# 12-DSP_PROCESSOR_2-OF-3.net
KiCad netlist of a schematic drawn in Altium Designer
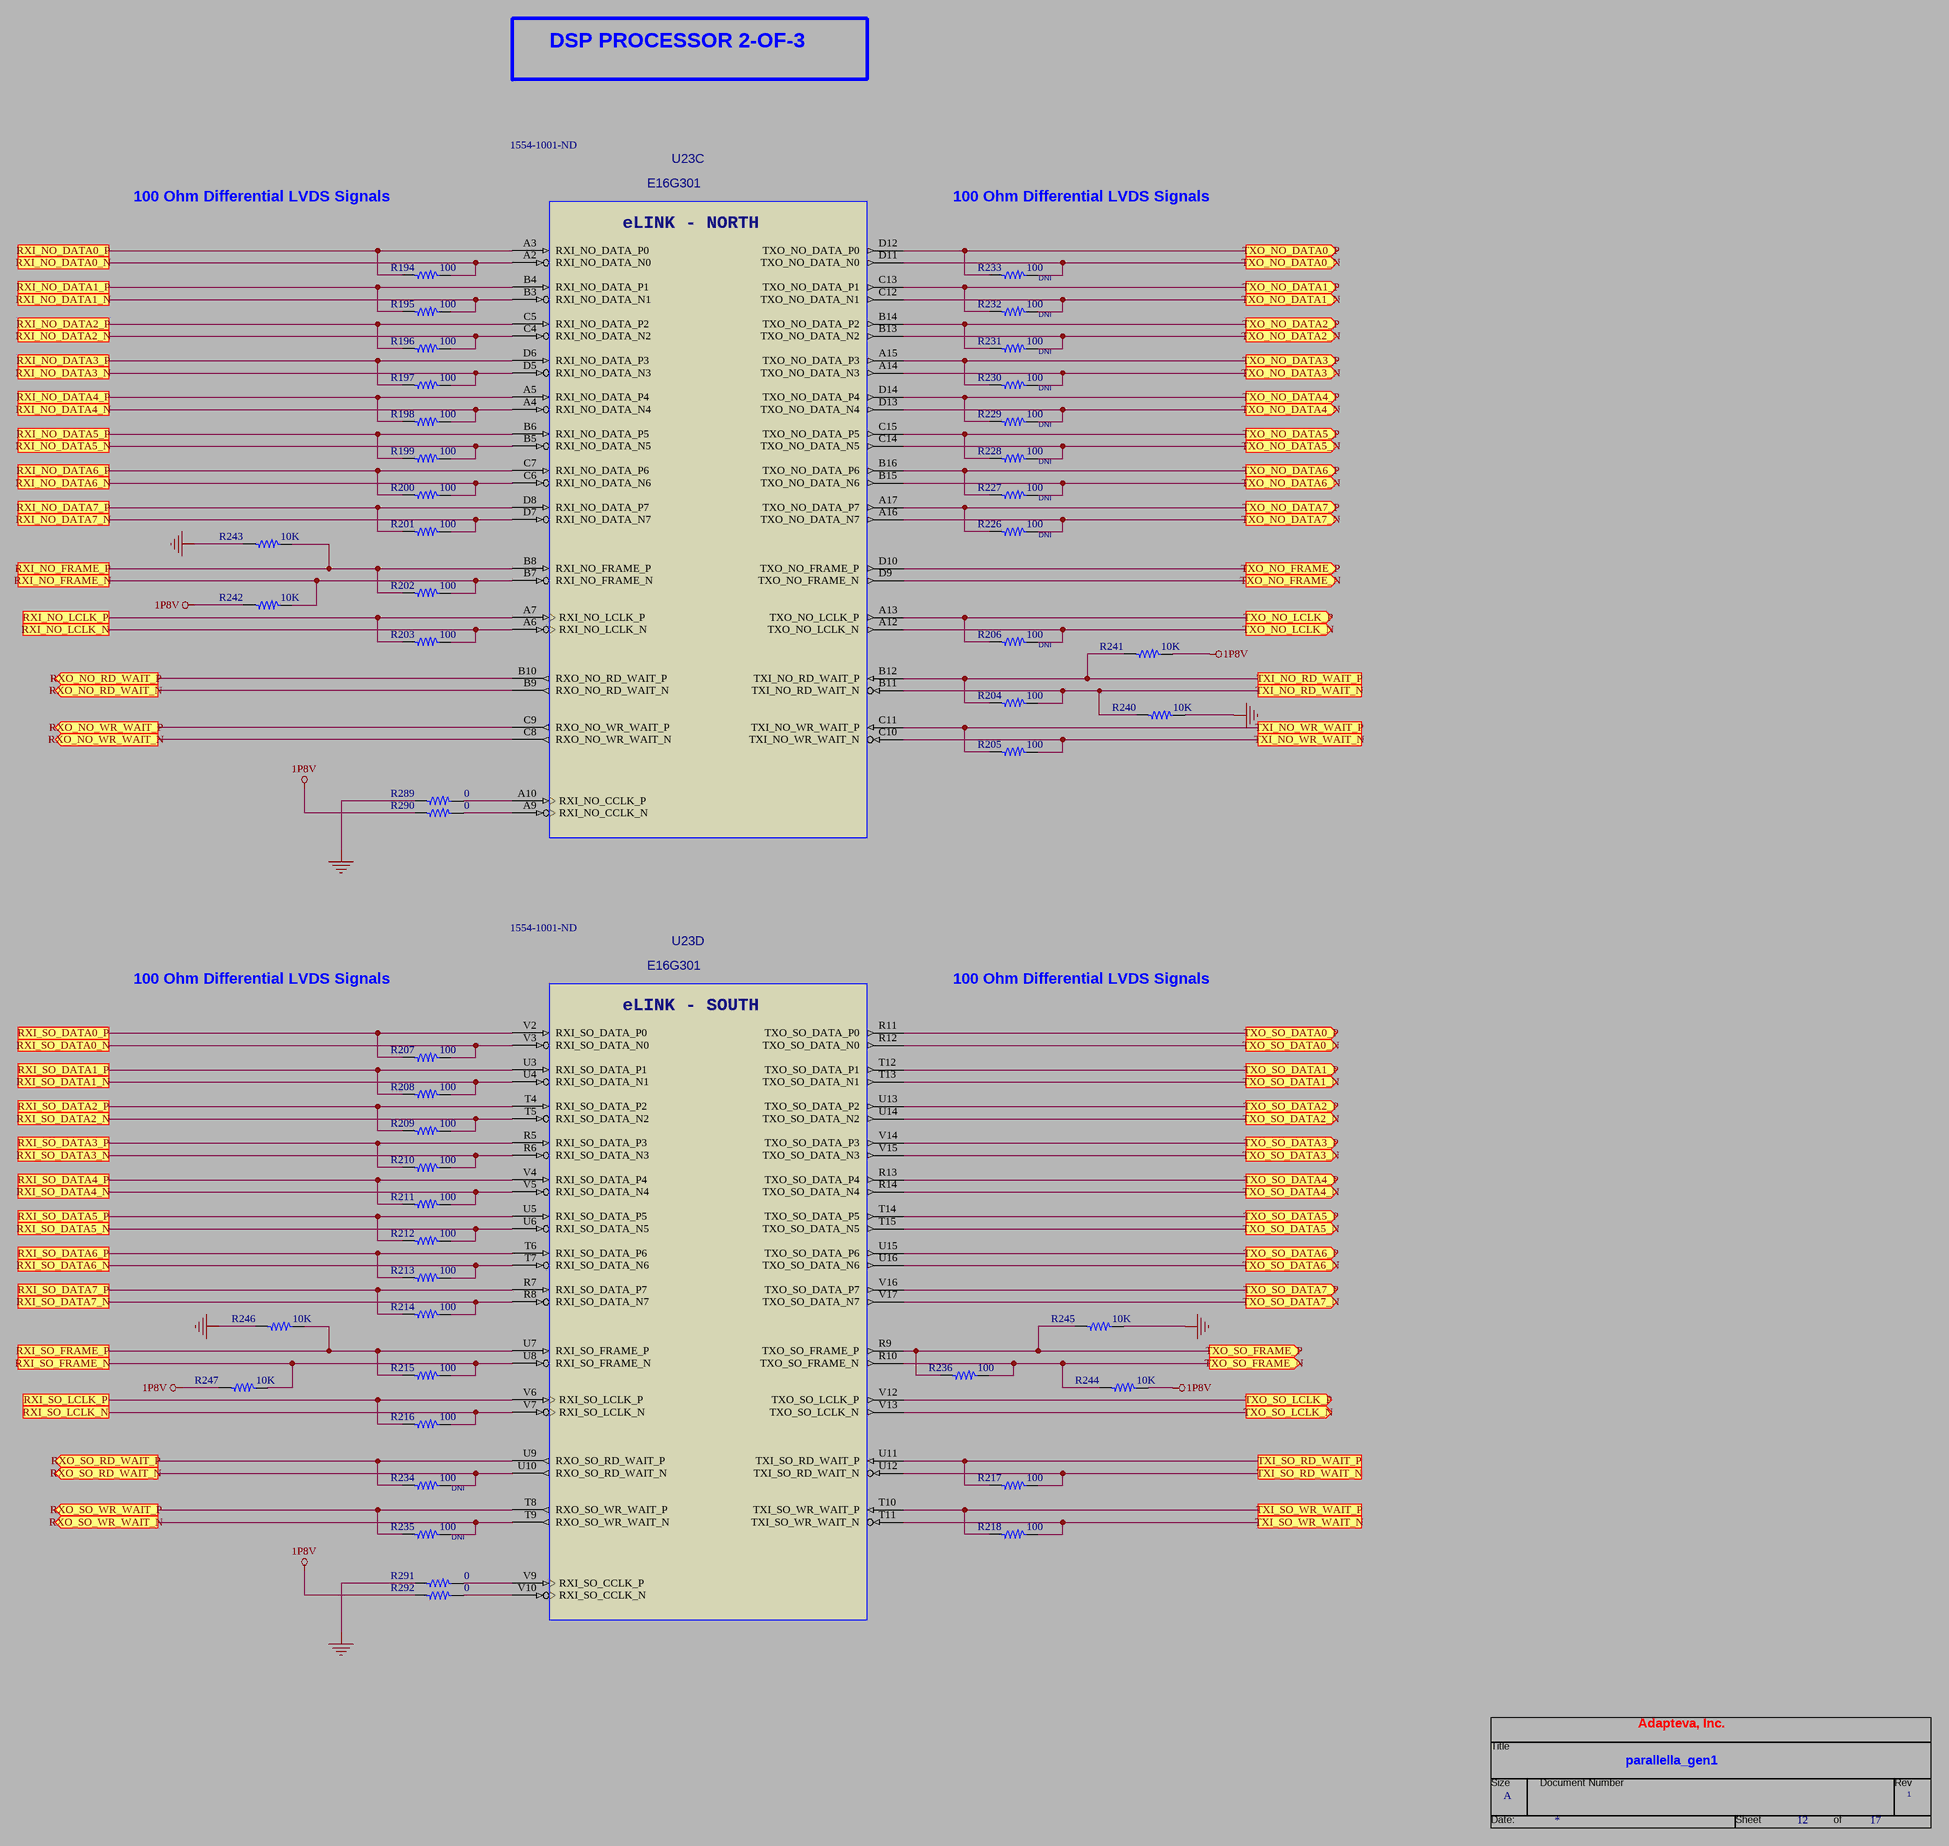
[diagram p0: 12-DSP PROCESSOR 2-OF-3.SchDoc]

(export (version "E")
  (design (tool "Eeschema 10.0.6"))
  (components
    (comp (ref "R194")
      (value "100")
      (footprint "R0402")
      (description "RES, 0402, 100, 1%")
      (fields (field (name "MFG PART NO") "CRCW0402100RFKED") (field (name "MFG") "VISHAY"))
      (libsource (lib "*") (part "RES0402_100"))
    )
    (comp (ref "R195")
      (value "100")
      (footprint "R0402")
      (description "RES, 0402, 100, 1%")
      (fields (field (name "MFG PART NO") "CRCW0402100RFKED") (field (name "MFG") "VISHAY"))
      (libsource (lib "*") (part "RES0402_100"))
    )
    (comp (ref "R196")
      (value "100")
      (footprint "R0402")
      (description "RES, 0402, 100, 1%")
      (fields (field (name "MFG PART NO") "CRCW0402100RFKED") (field (name "MFG") "VISHAY"))
      (libsource (lib "*") (part "RES0402_100"))
    )
    (comp (ref "R197")
      (value "100")
      (footprint "R0402")
      (description "RES, 0402, 100, 1%")
      (fields (field (name "MFG PART NO") "CRCW0402100RFKED") (field (name "MFG") "VISHAY"))
      (libsource (lib "*") (part "RES0402_100"))
    )
    (comp (ref "R198")
      (value "100")
      (footprint "R0402")
      (description "RES, 0402, 100, 1%")
      (fields (field (name "MFG PART NO") "CRCW0402100RFKED") (field (name "MFG") "VISHAY"))
      (libsource (lib "*") (part "RES0402_100"))
    )
    (comp (ref "R199")
      (value "100")
      (footprint "R0402")
      (description "RES, 0402, 100, 1%")
      (fields (field (name "MFG PART NO") "CRCW0402100RFKED") (field (name "MFG") "VISHAY"))
      (libsource (lib "*") (part "RES0402_100"))
    )
    (comp (ref "R200")
      (value "100")
      (footprint "R0402")
      (description "RES, 0402, 100, 1%")
      (fields (field (name "MFG PART NO") "CRCW0402100RFKED") (field (name "MFG") "VISHAY"))
      (libsource (lib "*") (part "RES0402_100"))
    )
    (comp (ref "R201")
      (value "100")
      (footprint "R0402")
      (description "RES, 0402, 100, 1%")
      (fields (field (name "MFG PART NO") "CRCW0402100RFKED") (field (name "MFG") "VISHAY"))
      (libsource (lib "*") (part "RES0402_100"))
    )
    (comp (ref "R202")
      (value "100")
      (footprint "R0402")
      (description "RES, 0402, 100, 1%")
      (fields (field (name "MFG PART NO") "CRCW0402100RFKED") (field (name "MFG") "VISHAY"))
      (libsource (lib "*") (part "RES0402_100"))
    )
    (comp (ref "R203")
      (value "100")
      (footprint "R0402")
      (description "RES, 0402, 100, 1%")
      (fields (field (name "MFG PART NO") "CRCW0402100RFKED") (field (name "MFG") "VISHAY"))
      (libsource (lib "*") (part "RES0402_100"))
    )
    (comp (ref "R204")
      (value "100")
      (footprint "R0402")
      (description "RES, 0402, 100, 1%")
      (fields (field (name "MFG PART NO") "CRCW0402100RFKED") (field (name "MFG") "VISHAY"))
      (libsource (lib "*") (part "RES0402_100"))
    )
    (comp (ref "R205")
      (value "100")
      (footprint "R0402")
      (description "RES, 0402, 100, 1%")
      (fields (field (name "MFG PART NO") "CRCW0402100RFKED") (field (name "MFG") "VISHAY"))
      (libsource (lib "*") (part "RES0402_100"))
    )
    (comp (ref "R206")
      (value "100")
      (footprint "R0402")
      (description "RES, 0402, 100, 1%")
      (fields
        (field (name "MFG PART NO") "CRCW0402100RFKED")
        (field (name "MFG") "VISHAY")
        (field (name "INSTALL") "DNI")
      )
      (libsource (lib "*") (part "RES0402_100"))
    )
    (comp (ref "R207")
      (value "100")
      (footprint "R0402")
      (description "RES, 0402, 100, 1%")
      (fields (field (name "MFG PART NO") "CRCW0402100RFKED") (field (name "MFG") "VISHAY"))
      (libsource (lib "*") (part "RES0402_100"))
    )
    (comp (ref "R208")
      (value "100")
      (footprint "R0402")
      (description "RES, 0402, 100, 1%")
      (fields (field (name "MFG PART NO") "CRCW0402100RFKED") (field (name "MFG") "VISHAY"))
      (libsource (lib "*") (part "RES0402_100"))
    )
    (comp (ref "R209")
      (value "100")
      (footprint "R0402")
      (description "RES, 0402, 100, 1%")
      (fields (field (name "MFG PART NO") "CRCW0402100RFKED") (field (name "MFG") "VISHAY"))
      (libsource (lib "*") (part "RES0402_100"))
    )
    (comp (ref "R210")
      (value "100")
      (footprint "R0402")
      (description "RES, 0402, 100, 1%")
      (fields (field (name "MFG PART NO") "CRCW0402100RFKED") (field (name "MFG") "VISHAY"))
      (libsource (lib "*") (part "RES0402_100"))
    )
    (comp (ref "R211")
      (value "100")
      (footprint "R0402")
      (description "RES, 0402, 100, 1%")
      (fields (field (name "MFG PART NO") "CRCW0402100RFKED") (field (name "MFG") "VISHAY"))
      (libsource (lib "*") (part "RES0402_100"))
    )
    (comp (ref "R212")
      (value "100")
      (footprint "R0402")
      (description "RES, 0402, 100, 1%")
      (fields (field (name "MFG PART NO") "CRCW0402100RFKED") (field (name "MFG") "VISHAY"))
      (libsource (lib "*") (part "RES0402_100"))
    )
    (comp (ref "R213")
      (value "100")
      (footprint "R0402")
      (description "RES, 0402, 100, 1%")
      (fields (field (name "MFG PART NO") "CRCW0402100RFKED") (field (name "MFG") "VISHAY"))
      (libsource (lib "*") (part "RES0402_100"))
    )
    (comp (ref "R214")
      (value "100")
      (footprint "R0402")
      (description "RES, 0402, 100, 1%")
      (fields (field (name "MFG PART NO") "CRCW0402100RFKED") (field (name "MFG") "VISHAY"))
      (libsource (lib "*") (part "RES0402_100"))
    )
    (comp (ref "R215")
      (value "100")
      (footprint "R0402")
      (description "RES, 0402, 100, 1%")
      (fields (field (name "MFG PART NO") "CRCW0402100RFKED") (field (name "MFG") "VISHAY"))
      (libsource (lib "*") (part "RES0402_100"))
    )
    (comp (ref "R216")
      (value "100")
      (footprint "R0402")
      (description "RES, 0402, 100, 1%")
      (fields (field (name "MFG PART NO") "CRCW0402100RFKED") (field (name "MFG") "VISHAY"))
      (libsource (lib "*") (part "RES0402_100"))
    )
    (comp (ref "R217")
      (value "100")
      (footprint "R0402")
      (description "RES, 0402, 100, 1%")
      (fields (field (name "MFG PART NO") "CRCW0402100RFKED") (field (name "MFG") "VISHAY"))
      (libsource (lib "*") (part "RES0402_100"))
    )
    (comp (ref "R218")
      (value "100")
      (footprint "R0402")
      (description "RES, 0402, 100, 1%")
      (fields (field (name "MFG PART NO") "CRCW0402100RFKED") (field (name "MFG") "VISHAY"))
      (libsource (lib "*") (part "RES0402_100"))
    )
    (comp (ref "R226")
      (value "100")
      (footprint "R0402")
      (description "RES, 0402, 100, 1%")
      (fields
        (field (name "MFG PART NO") "CRCW0402100RFKED")
        (field (name "MFG") "VISHAY")
        (field (name "INSTALL") "DNI")
      )
      (libsource (lib "*") (part "RES0402_100"))
    )
    (comp (ref "R227")
      (value "100")
      (footprint "R0402")
      (description "RES, 0402, 100, 1%")
      (fields
        (field (name "MFG PART NO") "CRCW0402100RFKED")
        (field (name "MFG") "VISHAY")
        (field (name "INSTALL") "DNI")
      )
      (libsource (lib "*") (part "RES0402_100"))
    )
    (comp (ref "R228")
      (value "100")
      (footprint "R0402")
      (description "RES, 0402, 100, 1%")
      (fields
        (field (name "MFG PART NO") "CRCW0402100RFKED")
        (field (name "MFG") "VISHAY")
        (field (name "INSTALL") "DNI")
      )
      (libsource (lib "*") (part "RES0402_100"))
    )
    (comp (ref "R229")
      (value "100")
      (footprint "R0402")
      (description "RES, 0402, 100, 1%")
      (fields
        (field (name "MFG PART NO") "CRCW0402100RFKED")
        (field (name "MFG") "VISHAY")
        (field (name "INSTALL") "DNI")
      )
      (libsource (lib "*") (part "RES0402_100"))
    )
    (comp (ref "R230")
      (value "100")
      (footprint "R0402")
      (description "RES, 0402, 100, 1%")
      (fields
        (field (name "MFG PART NO") "CRCW0402100RFKED")
        (field (name "MFG") "VISHAY")
        (field (name "INSTALL") "DNI")
      )
      (libsource (lib "*") (part "RES0402_100"))
    )
    (comp (ref "R231")
      (value "100")
      (footprint "R0402")
      (description "RES, 0402, 100, 1%")
      (fields
        (field (name "MFG PART NO") "CRCW0402100RFKED")
        (field (name "MFG") "VISHAY")
        (field (name "INSTALL") "DNI")
      )
      (libsource (lib "*") (part "RES0402_100"))
    )
    (comp (ref "R232")
      (value "100")
      (footprint "R0402")
      (description "RES, 0402, 100, 1%")
      (fields
        (field (name "MFG PART NO") "CRCW0402100RFKED")
        (field (name "MFG") "VISHAY")
        (field (name "INSTALL") "DNI")
      )
      (libsource (lib "*") (part "RES0402_100"))
    )
    (comp (ref "R233")
      (value "100")
      (footprint "R0402")
      (description "RES, 0402, 100, 1%")
      (fields
        (field (name "MFG PART NO") "CRCW0402100RFKED")
        (field (name "MFG") "VISHAY")
        (field (name "INSTALL") "DNI")
      )
      (libsource (lib "*") (part "RES0402_100"))
    )
    (comp (ref "R234")
      (value "100")
      (footprint "R0402")
      (description "RES, 0402, 100, 1%")
      (fields
        (field (name "MFG PART NO") "CRCW0402100RFKED")
        (field (name "MFG") "VISHAY")
        (field (name "INSTALL") "DNI")
      )
      (libsource (lib "*") (part "RES0402_100"))
    )
    (comp (ref "R235")
      (value "100")
      (footprint "R0402")
      (description "RES, 0402, 100, 1%")
      (fields
        (field (name "MFG PART NO") "CRCW0402100RFKED")
        (field (name "MFG") "VISHAY")
        (field (name "INSTALL") "DNI")
      )
      (libsource (lib "*") (part "RES0402_100"))
    )
    (comp (ref "R236")
      (value "100")
      (footprint "R0402")
      (description "RES, 0402, 100, 1%")
      (fields (field (name "MFG PART NO") "CRCW0402100RFKED") (field (name "MFG") "VISHAY"))
      (libsource (lib "*") (part "RES0402_100"))
    )
    (comp (ref "R240")
      (value "10K")
      (footprint "R0402")
      (description "RES, 0402, 10K")
      (fields (field (name "MFG") "VISHAY") (field (name "MFG PART NO") "CRCW040210K0FKED"))
      (libsource (lib "*") (part "RES0402_10K"))
    )
    (comp (ref "R241")
      (value "10K")
      (footprint "R0402")
      (description "RES, 0402, 10K")
      (fields (field (name "MFG") "VISHAY") (field (name "MFG PART NO") "CRCW040210K0FKED"))
      (libsource (lib "*") (part "RES0402_10K"))
    )
    (comp (ref "R242")
      (value "10K")
      (footprint "R0402")
      (description "RES, 0402, 10K")
      (fields (field (name "MFG") "VISHAY") (field (name "MFG PART NO") "CRCW040210K0FKED"))
      (libsource (lib "*") (part "RES0402_10K"))
    )
    (comp (ref "R243")
      (value "10K")
      (footprint "R0402")
      (description "RES, 0402, 10K")
      (fields (field (name "MFG") "VISHAY") (field (name "MFG PART NO") "CRCW040210K0FKED"))
      (libsource (lib "*") (part "RES0402_10K"))
    )
    (comp (ref "R244")
      (value "10K")
      (footprint "R0402")
      (description "RES, 0402, 10K")
      (fields (field (name "MFG") "VISHAY") (field (name "MFG PART NO") "CRCW040210K0FKED"))
      (libsource (lib "*") (part "RES0402_10K"))
    )
    (comp (ref "R245")
      (value "10K")
      (footprint "R0402")
      (description "RES, 0402, 10K")
      (fields (field (name "MFG") "VISHAY") (field (name "MFG PART NO") "CRCW040210K0FKED"))
      (libsource (lib "*") (part "RES0402_10K"))
    )
    (comp (ref "R246")
      (value "10K")
      (footprint "R0402")
      (description "RES, 0402, 10K")
      (fields (field (name "MFG") "VISHAY") (field (name "MFG PART NO") "CRCW040210K0FKED"))
      (libsource (lib "*") (part "RES0402_10K"))
    )
    (comp (ref "R247")
      (value "10K")
      (footprint "R0402")
      (description "RES, 0402, 10K")
      (fields (field (name "MFG") "VISHAY") (field (name "MFG PART NO") "CRCW040210K0FKED"))
      (libsource (lib "*") (part "RES0402_10K"))
    )
    (comp (ref "R289")
      (value "0")
      (footprint "R0402")
      (description "RES, 0402, 0 OHM, 1%")
      (fields (field (name "MFG") "VISHAY") (field (name "MFG PART NO") "CRCW04020000Z0ED"))
      (libsource (lib "*") (part "RES0402_0"))
    )
    (comp (ref "R290")
      (value "0")
      (footprint "R0402")
      (description "RES, 0402, 0 OHM, 1%")
      (fields (field (name "MFG") "VISHAY") (field (name "MFG PART NO") "CRCW04020000Z0ED"))
      (libsource (lib "*") (part "RES0402_0"))
    )
    (comp (ref "R291")
      (value "0")
      (footprint "R0402")
      (description "RES, 0402, 0 OHM, 1%")
      (fields (field (name "MFG") "VISHAY") (field (name "MFG PART NO") "CRCW04020000Z0ED"))
      (libsource (lib "*") (part "RES0402_0"))
    )
    (comp (ref "R292")
      (value "0")
      (footprint "R0402")
      (description "RES, 0402, 0 OHM, 1%")
      (fields (field (name "MFG") "VISHAY") (field (name "MFG PART NO") "CRCW04020000Z0ED"))
      (libsource (lib "*") (part "RES0402_0"))
    )
    (comp (ref "U23")
      (value "16-CORE MICROPROCESSOR")
      (footprint "BGA324_15SQX1P5_P8MMP")
      (description "IC, 16-CORE MICROPROCESSOR, ADAPTEVA, E16G301, BGA324")
      (fields (field (name "VENDOR PN") "E16G301") (field (name "SUPPLIER PART NUMBER 1") "1554-1001-ND"))
      (libsource (lib "*") (part "EPIPHANY_E16G301"))
    )
  )
  (nets
    (net (code "1") (name "/RXI_NO_DATA0_N") (class "Default")
      (node (ref "R194") (pin "2") (pinfunction "2_2") (pintype "passive"))
      (node (ref "U23") (pin "A2") (pinfunction "RXI_NO_DATA_N0_A2") (pintype "input"))
    )
    (net (code "2") (name "/RXI_NO_DATA0_P") (class "Default")
      (node (ref "R194") (pin "1") (pinfunction "1_1") (pintype "passive"))
      (node (ref "U23") (pin "A3") (pinfunction "RXI_NO_DATA_P0_A3") (pintype "input"))
    )
    (net (code "3") (name "/RXI_NO_DATA1_N") (class "Default")
      (node (ref "R195") (pin "2") (pinfunction "2_2") (pintype "passive"))
      (node (ref "U23") (pin "B3") (pinfunction "RXI_NO_DATA_N1_B3") (pintype "input"))
    )
    (net (code "4") (name "/RXI_NO_DATA1_P") (class "Default")
      (node (ref "R195") (pin "1") (pinfunction "1_1") (pintype "passive"))
      (node (ref "U23") (pin "B4") (pinfunction "RXI_NO_DATA_P1_B4") (pintype "input"))
    )
    (net (code "5") (name "/RXI_NO_DATA2_N") (class "Default")
      (node (ref "R196") (pin "2") (pinfunction "2_2") (pintype "passive"))
      (node (ref "U23") (pin "C4") (pinfunction "RXI_NO_DATA_N2_C4") (pintype "input"))
    )
    (net (code "6") (name "/RXI_NO_DATA2_P") (class "Default")
      (node (ref "R196") (pin "1") (pinfunction "1_1") (pintype "passive"))
      (node (ref "U23") (pin "C5") (pinfunction "RXI_NO_DATA_P2_C5") (pintype "input"))
    )
    (net (code "7") (name "/RXI_NO_DATA3_N") (class "Default")
      (node (ref "R197") (pin "2") (pinfunction "2_2") (pintype "passive"))
      (node (ref "U23") (pin "D5") (pinfunction "RXI_NO_DATA_N3_D5") (pintype "input"))
    )
    (net (code "8") (name "/RXI_NO_DATA3_P") (class "Default")
      (node (ref "R197") (pin "1") (pinfunction "1_1") (pintype "passive"))
      (node (ref "U23") (pin "D6") (pinfunction "RXI_NO_DATA_P3_D6") (pintype "input"))
    )
    (net (code "9") (name "/RXI_NO_DATA4_N") (class "Default")
      (node (ref "R198") (pin "2") (pinfunction "2_2") (pintype "passive"))
      (node (ref "U23") (pin "A4") (pinfunction "RXI_NO_DATA_N4_A4") (pintype "input"))
    )
    (net (code "10") (name "/RXI_NO_DATA4_P") (class "Default")
      (node (ref "R198") (pin "1") (pinfunction "1_1") (pintype "passive"))
      (node (ref "U23") (pin "A5") (pinfunction "RXI_NO_DATA_P4_A5") (pintype "input"))
    )
    (net (code "11") (name "/RXI_NO_DATA5_N") (class "Default")
      (node (ref "R199") (pin "2") (pinfunction "2_2") (pintype "passive"))
      (node (ref "U23") (pin "B5") (pinfunction "RXI_NO_DATA_N5_B5") (pintype "input"))
    )
    (net (code "12") (name "/RXI_NO_DATA5_P") (class "Default")
      (node (ref "R199") (pin "1") (pinfunction "1_1") (pintype "passive"))
      (node (ref "U23") (pin "B6") (pinfunction "RXI_NO_DATA_P5_B6") (pintype "input"))
    )
    (net (code "13") (name "/RXI_NO_DATA6_N") (class "Default")
      (node (ref "R200") (pin "2") (pinfunction "2_2") (pintype "passive"))
      (node (ref "U23") (pin "C6") (pinfunction "RXI_NO_DATA_N6_C6") (pintype "input"))
    )
    (net (code "14") (name "/RXI_NO_DATA6_P") (class "Default")
      (node (ref "R200") (pin "1") (pinfunction "1_1") (pintype "passive"))
      (node (ref "U23") (pin "C7") (pinfunction "RXI_NO_DATA_P6_C7") (pintype "input"))
    )
    (net (code "15") (name "/RXI_NO_DATA7_N") (class "Default")
      (node (ref "R201") (pin "2") (pinfunction "2_2") (pintype "passive"))
      (node (ref "U23") (pin "D7") (pinfunction "RXI_NO_DATA_N7_D7") (pintype "input"))
    )
    (net (code "16") (name "/RXI_NO_DATA7_P") (class "Default")
      (node (ref "R201") (pin "1") (pinfunction "1_1") (pintype "passive"))
      (node (ref "U23") (pin "D8") (pinfunction "RXI_NO_DATA_P7_D8") (pintype "input"))
    )
    (net (code "17") (name "/RXI_NO_FRAME_N") (class "Default")
      (node (ref "R202") (pin "2") (pinfunction "2_2") (pintype "passive"))
      (node (ref "R242") (pin "2") (pinfunction "2_2") (pintype "passive"))
      (node (ref "U23") (pin "B7") (pinfunction "RXI_NO_FRAME_N_B7") (pintype "input"))
    )
    (net (code "18") (name "/RXI_NO_FRAME_P") (class "Default")
      (node (ref "R202") (pin "1") (pinfunction "1_1") (pintype "passive"))
      (node (ref "R243") (pin "2") (pinfunction "2_2") (pintype "passive"))
      (node (ref "U23") (pin "B8") (pinfunction "RXI_NO_FRAME_P_B8") (pintype "input"))
    )
    (net (code "19") (name "/RXI_NO_LCLK_N") (class "Default")
      (node (ref "R203") (pin "2") (pinfunction "2_2") (pintype "passive"))
      (node (ref "U23") (pin "A6") (pinfunction "RXI_NO_LCLK_N_A6") (pintype "input"))
    )
    (net (code "20") (name "/RXI_NO_LCLK_P") (class "Default")
      (node (ref "R203") (pin "1") (pinfunction "1_1") (pintype "passive"))
      (node (ref "U23") (pin "A7") (pinfunction "RXI_NO_LCLK_P_A7") (pintype "input"))
    )
    (net (code "21") (name "/RXI_SO_DATA0_N") (class "Default")
      (node (ref "R207") (pin "2") (pinfunction "2_2") (pintype "passive"))
      (node (ref "U23") (pin "V3") (pinfunction "RXI_SO_DATA_N0_V3") (pintype "input"))
    )
    (net (code "22") (name "/RXI_SO_DATA0_P") (class "Default")
      (node (ref "R207") (pin "1") (pinfunction "1_1") (pintype "passive"))
      (node (ref "U23") (pin "V2") (pinfunction "RXI_SO_DATA_P0_V2") (pintype "input"))
    )
    (net (code "23") (name "/RXI_SO_DATA1_N") (class "Default")
      (node (ref "R208") (pin "2") (pinfunction "2_2") (pintype "passive"))
      (node (ref "U23") (pin "U4") (pinfunction "RXI_SO_DATA_N1_U4") (pintype "input"))
    )
    (net (code "24") (name "/RXI_SO_DATA1_P") (class "Default")
      (node (ref "R208") (pin "1") (pinfunction "1_1") (pintype "passive"))
      (node (ref "U23") (pin "U3") (pinfunction "RXI_SO_DATA_P1_U3") (pintype "input"))
    )
    (net (code "25") (name "/RXI_SO_DATA2_N") (class "Default")
      (node (ref "R209") (pin "2") (pinfunction "2_2") (pintype "passive"))
      (node (ref "U23") (pin "T5") (pinfunction "RXI_SO_DATA_N2_T5") (pintype "input"))
    )
    (net (code "26") (name "/RXI_SO_DATA2_P") (class "Default")
      (node (ref "R209") (pin "1") (pinfunction "1_1") (pintype "passive"))
      (node (ref "U23") (pin "T4") (pinfunction "RXI_SO_DATA_P2_T4") (pintype "input"))
    )
    (net (code "27") (name "/RXI_SO_DATA3_N") (class "Default")
      (node (ref "R210") (pin "2") (pinfunction "2_2") (pintype "passive"))
      (node (ref "U23") (pin "R6") (pinfunction "RXI_SO_DATA_N3_R6") (pintype "input"))
    )
    (net (code "28") (name "/RXI_SO_DATA3_P") (class "Default")
      (node (ref "R210") (pin "1") (pinfunction "1_1") (pintype "passive"))
      (node (ref "U23") (pin "R5") (pinfunction "RXI_SO_DATA_P3_R5") (pintype "input"))
    )
    (net (code "29") (name "/RXI_SO_DATA4_N") (class "Default")
      (node (ref "R211") (pin "2") (pinfunction "2_2") (pintype "passive"))
      (node (ref "U23") (pin "V5") (pinfunction "RXI_SO_DATA_N4_V5") (pintype "input"))
    )
    (net (code "30") (name "/RXI_SO_DATA4_P") (class "Default")
      (node (ref "R211") (pin "1") (pinfunction "1_1") (pintype "passive"))
      (node (ref "U23") (pin "V4") (pinfunction "RXI_SO_DATA_P4_V4") (pintype "input"))
    )
    (net (code "31") (name "/RXI_SO_DATA5_N") (class "Default")
      (node (ref "R212") (pin "2") (pinfunction "2_2") (pintype "passive"))
      (node (ref "U23") (pin "U6") (pinfunction "RXI_SO_DATA_N5_U6") (pintype "input"))
    )
    (net (code "32") (name "/RXI_SO_DATA5_P") (class "Default")
      (node (ref "R212") (pin "1") (pinfunction "1_1") (pintype "passive"))
      (node (ref "U23") (pin "U5") (pinfunction "RXI_SO_DATA_P5_U5") (pintype "input"))
    )
    (net (code "33") (name "/RXI_SO_DATA6_N") (class "Default")
      (node (ref "R213") (pin "2") (pinfunction "2_2") (pintype "passive"))
      (node (ref "U23") (pin "T7") (pinfunction "RXI_SO_DATA_N6_T7") (pintype "input"))
    )
    (net (code "34") (name "/RXI_SO_DATA6_P") (class "Default")
      (node (ref "R213") (pin "1") (pinfunction "1_1") (pintype "passive"))
      (node (ref "U23") (pin "T6") (pinfunction "RXI_SO_DATA_P6_T6") (pintype "input"))
    )
    (net (code "35") (name "/RXI_SO_DATA7_N") (class "Default")
      (node (ref "R214") (pin "2") (pinfunction "2_2") (pintype "passive"))
      (node (ref "U23") (pin "R8") (pinfunction "RXI_SO_DATA_N7_R8") (pintype "input"))
    )
    (net (code "36") (name "/RXI_SO_DATA7_P") (class "Default")
      (node (ref "R214") (pin "1") (pinfunction "1_1") (pintype "passive"))
      (node (ref "U23") (pin "R7") (pinfunction "RXI_SO_DATA_P7_R7") (pintype "input"))
    )
    (net (code "37") (name "/RXI_SO_FRAME_N") (class "Default")
      (node (ref "R215") (pin "2") (pinfunction "2_2") (pintype "passive"))
      (node (ref "R247") (pin "2") (pinfunction "2_2") (pintype "passive"))
      (node (ref "U23") (pin "U8") (pinfunction "RXI_SO_FRAME_N_U8") (pintype "input"))
    )
    (net (code "38") (name "/RXI_SO_FRAME_P") (class "Default")
      (node (ref "R215") (pin "1") (pinfunction "1_1") (pintype "passive"))
      (node (ref "R246") (pin "2") (pinfunction "2_2") (pintype "passive"))
      (node (ref "U23") (pin "U7") (pinfunction "RXI_SO_FRAME_P_U7") (pintype "input"))
    )
    (net (code "39") (name "/RXI_SO_LCLK_N") (class "Default")
      (node (ref "R216") (pin "2") (pinfunction "2_2") (pintype "passive"))
      (node (ref "U23") (pin "V7") (pinfunction "RXI_SO_LCLK_N_V7") (pintype "input"))
    )
    (net (code "40") (name "/RXI_SO_LCLK_P") (class "Default")
      (node (ref "R216") (pin "1") (pinfunction "1_1") (pintype "passive"))
      (node (ref "U23") (pin "V6") (pinfunction "RXI_SO_LCLK_P_V6") (pintype "input"))
    )
    (net (code "41") (name "/RXO_NO_RD_WAIT_N") (class "Default")
      (node (ref "U23") (pin "B9") (pinfunction "RXO_NO_RD_WAIT_N_B9") (pintype "output"))
    )
    (net (code "42") (name "/RXO_NO_RD_WAIT_P") (class "Default")
      (node (ref "U23") (pin "B10") (pinfunction "RXO_NO_RD_WAIT_P_B10") (pintype "output"))
    )
    (net (code "43") (name "/RXO_NO_WR_WAIT_N") (class "Default")
      (node (ref "U23") (pin "C8") (pinfunction "RXO_NO_WR_WAIT_N_C8") (pintype "output"))
    )
    (net (code "44") (name "/RXO_NO_WR_WAIT_P") (class "Default")
      (node (ref "U23") (pin "C9") (pinfunction "RXO_NO_WR_WAIT_P_C9") (pintype "output"))
    )
    (net (code "45") (name "/RXO_SO_RD_WAIT_N") (class "Default")
      (node (ref "R234") (pin "2") (pinfunction "2_2") (pintype "passive"))
      (node (ref "U23") (pin "U10") (pinfunction "RXO_SO_RD_WAIT_N_U10") (pintype "output"))
    )
    (net (code "46") (name "/RXO_SO_RD_WAIT_P") (class "Default")
      (node (ref "R234") (pin "1") (pinfunction "1_1") (pintype "passive"))
      (node (ref "U23") (pin "U9") (pinfunction "RXO_SO_RD_WAIT_P_U9") (pintype "output"))
    )
    (net (code "47") (name "/RXO_SO_WR_WAIT_N") (class "Default")
      (node (ref "R235") (pin "2") (pinfunction "2_2") (pintype "passive"))
      (node (ref "U23") (pin "T9") (pinfunction "RXO_SO_WR_WAIT_N_T9") (pintype "output"))
    )
    (net (code "48") (name "/RXO_SO_WR_WAIT_P") (class "Default")
      (node (ref "R235") (pin "1") (pinfunction "1_1") (pintype "passive"))
      (node (ref "U23") (pin "T8") (pinfunction "RXO_SO_WR_WAIT_P_T8") (pintype "output"))
    )
    (net (code "49") (name "/TXI_NO_RD_WAIT_N") (class "Default")
      (node (ref "R204") (pin "2") (pinfunction "2_2") (pintype "passive"))
      (node (ref "R240") (pin "1") (pinfunction "1_1") (pintype "passive"))
      (node (ref "U23") (pin "B11") (pinfunction "TXI_NO_RD_WAIT_N_B11") (pintype "input"))
    )
    (net (code "50") (name "/TXI_NO_RD_WAIT_P") (class "Default")
      (node (ref "R204") (pin "1") (pinfunction "1_1") (pintype "passive"))
      (node (ref "R241") (pin "1") (pinfunction "1_1") (pintype "passive"))
      (node (ref "U23") (pin "B12") (pinfunction "TXI_NO_RD_WAIT_P_B12") (pintype "input"))
    )
    (net (code "51") (name "/TXI_NO_WR_WAIT_N") (class "Default")
      (node (ref "R205") (pin "2") (pinfunction "2_2") (pintype "passive"))
      (node (ref "U23") (pin "C10") (pinfunction "TXI_NO_WR_WAIT_N_C10") (pintype "input"))
    )
    (net (code "52") (name "/TXI_NO_WR_WAIT_P") (class "Default")
      (node (ref "R205") (pin "1") (pinfunction "1_1") (pintype "passive"))
      (node (ref "U23") (pin "C11") (pinfunction "TXI_NO_WR_WAIT_P_C11") (pintype "input"))
    )
    (net (code "53") (name "/TXI_SO_RD_WAIT_N") (class "Default")
      (node (ref "R217") (pin "2") (pinfunction "2_2") (pintype "passive"))
      (node (ref "U23") (pin "U12") (pinfunction "TXI_SO_RD_WAIT_N_U12") (pintype "input"))
    )
    (net (code "54") (name "/TXI_SO_RD_WAIT_P") (class "Default")
      (node (ref "R217") (pin "1") (pinfunction "1_1") (pintype "passive"))
      (node (ref "U23") (pin "U11") (pinfunction "TXI_SO_RD_WAIT_P_U11") (pintype "input"))
    )
    (net (code "55") (name "/TXI_SO_WR_WAIT_N") (class "Default")
      (node (ref "R218") (pin "2") (pinfunction "2_2") (pintype "passive"))
      (node (ref "U23") (pin "T11") (pinfunction "TXI_SO_WR_WAIT_N_T11") (pintype "input"))
    )
    (net (code "56") (name "/TXI_SO_WR_WAIT_P") (class "Default")
      (node (ref "R218") (pin "1") (pinfunction "1_1") (pintype "passive"))
      (node (ref "U23") (pin "T10") (pinfunction "TXI_SO_WR_WAIT_P_T10") (pintype "input"))
    )
    (net (code "57") (name "/TXO_NO_DATA0_N") (class "Default")
      (node (ref "R233") (pin "2") (pinfunction "2_2") (pintype "passive"))
      (node (ref "U23") (pin "D11") (pinfunction "TXO_NO_DATA_N0_D11") (pintype "output"))
    )
    (net (code "58") (name "/TXO_NO_DATA0_P") (class "Default")
      (node (ref "R233") (pin "1") (pinfunction "1_1") (pintype "passive"))
      (node (ref "U23") (pin "D12") (pinfunction "TXO_NO_DATA_P0_D12") (pintype "output"))
    )
    (net (code "59") (name "/TXO_NO_DATA1_N") (class "Default")
      (node (ref "R232") (pin "2") (pinfunction "2_2") (pintype "passive"))
      (node (ref "U23") (pin "C12") (pinfunction "TXO_NO_DATA_N1_C12") (pintype "output"))
    )
    (net (code "60") (name "/TXO_NO_DATA1_P") (class "Default")
      (node (ref "R232") (pin "1") (pinfunction "1_1") (pintype "passive"))
      (node (ref "U23") (pin "C13") (pinfunction "TXO_NO_DATA_P1_C13") (pintype "output"))
    )
    (net (code "61") (name "/TXO_NO_DATA2_N") (class "Default")
      (node (ref "R231") (pin "2") (pinfunction "2_2") (pintype "passive"))
      (node (ref "U23") (pin "B13") (pinfunction "TXO_NO_DATA_N2_B13") (pintype "output"))
    )
    (net (code "62") (name "/TXO_NO_DATA2_P") (class "Default")
      (node (ref "R231") (pin "1") (pinfunction "1_1") (pintype "passive"))
      (node (ref "U23") (pin "B14") (pinfunction "TXO_NO_DATA_P2_B14") (pintype "output"))
    )
    (net (code "63") (name "/TXO_NO_DATA3_N") (class "Default")
      (node (ref "R230") (pin "2") (pinfunction "2_2") (pintype "passive"))
      (node (ref "U23") (pin "A14") (pinfunction "TXO_NO_DATA_N3_A14") (pintype "output"))
    )
    (net (code "64") (name "/TXO_NO_DATA3_P") (class "Default")
      (node (ref "R230") (pin "1") (pinfunction "1_1") (pintype "passive"))
      (node (ref "U23") (pin "A15") (pinfunction "TXO_NO_DATA_P3_A15") (pintype "output"))
    )
    (net (code "65") (name "/TXO_NO_DATA4_N") (class "Default")
      (node (ref "R229") (pin "2") (pinfunction "2_2") (pintype "passive"))
      (node (ref "U23") (pin "D13") (pinfunction "TXO_NO_DATA_N4_D13") (pintype "output"))
    )
    (net (code "66") (name "/TXO_NO_DATA4_P") (class "Default")
      (node (ref "R229") (pin "1") (pinfunction "1_1") (pintype "passive"))
      (node (ref "U23") (pin "D14") (pinfunction "TXO_NO_DATA_P4_D14") (pintype "output"))
    )
    (net (code "67") (name "/TXO_NO_DATA5_N") (class "Default")
      (node (ref "R228") (pin "2") (pinfunction "2_2") (pintype "passive"))
      (node (ref "U23") (pin "C14") (pinfunction "TXO_NO_DATA_N5_C14") (pintype "output"))
    )
    (net (code "68") (name "/TXO_NO_DATA5_P") (class "Default")
      (node (ref "R228") (pin "1") (pinfunction "1_1") (pintype "passive"))
      (node (ref "U23") (pin "C15") (pinfunction "TXO_NO_DATA_P5_C15") (pintype "output"))
    )
    (net (code "69") (name "/TXO_NO_DATA6_N") (class "Default")
      (node (ref "R227") (pin "2") (pinfunction "2_2") (pintype "passive"))
      (node (ref "U23") (pin "B15") (pinfunction "TXO_NO_DATA_N6_B15") (pintype "output"))
    )
    (net (code "70") (name "/TXO_NO_DATA6_P") (class "Default")
      (node (ref "R227") (pin "1") (pinfunction "1_1") (pintype "passive"))
      (node (ref "U23") (pin "B16") (pinfunction "TXO_NO_DATA_P6_B16") (pintype "output"))
    )
    (net (code "71") (name "/TXO_NO_DATA7_N") (class "Default")
      (node (ref "R226") (pin "2") (pinfunction "2_2") (pintype "passive"))
      (node (ref "U23") (pin "A16") (pinfunction "TXO_NO_DATA_N7_A16") (pintype "output"))
    )
    (net (code "72") (name "/TXO_NO_DATA7_P") (class "Default")
      (node (ref "R226") (pin "1") (pinfunction "1_1") (pintype "passive"))
      (node (ref "U23") (pin "A17") (pinfunction "TXO_NO_DATA_P7_A17") (pintype "output"))
    )
    (net (code "73") (name "/TXO_NO_FRAME_N") (class "Default")
      (node (ref "U23") (pin "D9") (pinfunction "TXO_NO_FRAME_N_D9") (pintype "output"))
    )
    (net (code "74") (name "/TXO_NO_FRAME_P") (class "Default")
      (node (ref "U23") (pin "D10") (pinfunction "TXO_NO_FRAME_P_D10") (pintype "output"))
    )
    (net (code "75") (name "/TXO_NO_LCLK_N") (class "Default")
      (node (ref "R206") (pin "2") (pinfunction "2_2") (pintype "passive"))
      (node (ref "U23") (pin "A12") (pinfunction "TXO_NO_LCLK_N_A12") (pintype "output"))
    )
    (net (code "76") (name "/TXO_NO_LCLK_P") (class "Default")
      (node (ref "R206") (pin "1") (pinfunction "1_1") (pintype "passive"))
      (node (ref "U23") (pin "A13") (pinfunction "TXO_NO_LCLK_P_A13") (pintype "output"))
    )
    (net (code "77") (name "/TXO_SO_DATA0_N") (class "Default")
      (node (ref "U23") (pin "R12") (pinfunction "TXO_SO_DATA_N0_R12") (pintype "output"))
    )
    (net (code "78") (name "/TXO_SO_DATA0_P") (class "Default")
      (node (ref "U23") (pin "R11") (pinfunction "TXO_SO_DATA_P0_R11") (pintype "output"))
    )
    (net (code "79") (name "/TXO_SO_DATA1_N") (class "Default")
      (node (ref "U23") (pin "T13") (pinfunction "TXO_SO_DATA_N1_T13") (pintype "output"))
    )
    (net (code "80") (name "/TXO_SO_DATA1_P") (class "Default")
      (node (ref "U23") (pin "T12") (pinfunction "TXO_SO_DATA_P1_T12") (pintype "output"))
    )
    (net (code "81") (name "/TXO_SO_DATA2_N") (class "Default")
      (node (ref "U23") (pin "U14") (pinfunction "TXO_SO_DATA_N2_U14") (pintype "output"))
    )
    (net (code "82") (name "/TXO_SO_DATA2_P") (class "Default")
      (node (ref "U23") (pin "U13") (pinfunction "TXO_SO_DATA_P2_U13") (pintype "output"))
    )
    (net (code "83") (name "/TXO_SO_DATA3_N") (class "Default")
      (node (ref "U23") (pin "V15") (pinfunction "TXO_SO_DATA_N3_V15") (pintype "output"))
    )
    (net (code "84") (name "/TXO_SO_DATA3_P") (class "Default")
      (node (ref "U23") (pin "V14") (pinfunction "TXO_SO_DATA_P3_V14") (pintype "output"))
    )
    (net (code "85") (name "/TXO_SO_DATA4_N") (class "Default")
      (node (ref "U23") (pin "R14") (pinfunction "TXO_SO_DATA_N4_R14") (pintype "output"))
    )
    (net (code "86") (name "/TXO_SO_DATA4_P") (class "Default")
      (node (ref "U23") (pin "R13") (pinfunction "TXO_SO_DATA_P4_R13") (pintype "output"))
    )
    (net (code "87") (name "/TXO_SO_DATA5_N") (class "Default")
      (node (ref "U23") (pin "T15") (pinfunction "TXO_SO_DATA_N5_T15") (pintype "output"))
    )
    (net (code "88") (name "/TXO_SO_DATA5_P") (class "Default")
      (node (ref "U23") (pin "T14") (pinfunction "TXO_SO_DATA_P5_T14") (pintype "output"))
    )
    (net (code "89") (name "/TXO_SO_DATA6_N") (class "Default")
      (node (ref "U23") (pin "U16") (pinfunction "TXO_SO_DATA_N6_U16") (pintype "output"))
    )
    (net (code "90") (name "/TXO_SO_DATA6_P") (class "Default")
      (node (ref "U23") (pin "U15") (pinfunction "TXO_SO_DATA_P6_U15") (pintype "output"))
    )
    (net (code "91") (name "/TXO_SO_DATA7_N") (class "Default")
      (node (ref "U23") (pin "V17") (pinfunction "TXO_SO_DATA_N7_V17") (pintype "output"))
    )
    (net (code "92") (name "/TXO_SO_DATA7_P") (class "Default")
      (node (ref "U23") (pin "V16") (pinfunction "TXO_SO_DATA_P7_V16") (pintype "output"))
    )
    (net (code "93") (name "/TXO_SO_FRAME_N") (class "Default")
      (node (ref "R236") (pin "2") (pinfunction "2_2") (pintype "passive"))
      (node (ref "R244") (pin "1") (pinfunction "1_1") (pintype "passive"))
      (node (ref "U23") (pin "R10") (pinfunction "TXO_SO_FRAME_N_R10") (pintype "output"))
    )
    (net (code "94") (name "/TXO_SO_FRAME_P") (class "Default")
      (node (ref "R236") (pin "1") (pinfunction "1_1") (pintype "passive"))
      (node (ref "R245") (pin "1") (pinfunction "1_1") (pintype "passive"))
      (node (ref "U23") (pin "R9") (pinfunction "TXO_SO_FRAME_P_R9") (pintype "output"))
    )
    (net (code "95") (name "/TXO_SO_LCLK_N") (class "Default")
      (node (ref "U23") (pin "V13") (pinfunction "TXO_SO_LCLK_N_V13") (pintype "output"))
    )
    (net (code "96") (name "/TXO_SO_LCLK_P") (class "Default")
      (node (ref "U23") (pin "V12") (pinfunction "TXO_SO_LCLK_P_V12") (pintype "output"))
    )
    (net (code "97") (name "1P8V") (class "Default")
      (node (ref "R241") (pin "2") (pinfunction "2_2") (pintype "passive"))
      (node (ref "R242") (pin "1") (pinfunction "1_1") (pintype "passive"))
      (node (ref "R244") (pin "2") (pinfunction "2_2") (pintype "passive"))
      (node (ref "R247") (pin "1") (pinfunction "1_1") (pintype "passive"))
      (node (ref "R290") (pin "1") (pinfunction "1_1") (pintype "passive"))
      (node (ref "R292") (pin "1") (pinfunction "1_1") (pintype "passive"))
    )
    (net (code "98") (name "GND") (class "Default")
      (node (ref "R240") (pin "2") (pinfunction "2_2") (pintype "passive"))
      (node (ref "R243") (pin "1") (pinfunction "1_1") (pintype "passive"))
      (node (ref "R245") (pin "2") (pinfunction "2_2") (pintype "passive"))
      (node (ref "R246") (pin "1") (pinfunction "1_1") (pintype "passive"))
      (node (ref "R289") (pin "1") (pinfunction "1_1") (pintype "passive"))
      (node (ref "R291") (pin "1") (pinfunction "1_1") (pintype "passive"))
    )
    (net (code "99") (name "Net-(U23C-RXI_NO_CCLK_N)") (class "Default")
      (node (ref "R290") (pin "2") (pinfunction "2_2") (pintype "passive"))
      (node (ref "U23") (pin "A9") (pinfunction "RXI_NO_CCLK_N_A9") (pintype "input"))
    )
    (net (code "100") (name "Net-(U23C-RXI_NO_CCLK_P)") (class "Default")
      (node (ref "R289") (pin "2") (pinfunction "2_2") (pintype "passive"))
      (node (ref "U23") (pin "A10") (pinfunction "RXI_NO_CCLK_P_A10") (pintype "input"))
    )
    (net (code "101") (name "Net-(U23D-RXI_SO_CCLK_N)") (class "Default")
      (node (ref "R292") (pin "2") (pinfunction "2_2") (pintype "passive"))
      (node (ref "U23") (pin "V10") (pinfunction "RXI_SO_CCLK_N_V10") (pintype "input"))
    )
    (net (code "102") (name "Net-(U23D-RXI_SO_CCLK_P)") (class "Default")
      (node (ref "R291") (pin "2") (pinfunction "2_2") (pintype "passive"))
      (node (ref "U23") (pin "V9") (pinfunction "RXI_SO_CCLK_P_V9") (pintype "input"))
    )
  )
)
